# Sallen_key_bandpass.net
KiCad netlist of a schematic drawn in Altium Designer
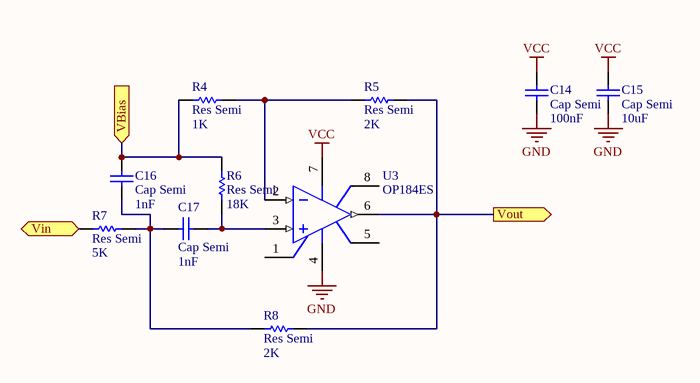
[diagram p0: Sallen_key_bandpass.SchDoc]

(export (version "E")
  (design (tool "Eeschema 10.0.6"))
  (components
    (comp (ref "C14")
      (value "Cap Semi")
      (footprint "C0805")
      (description "Capacitor (Semiconductor SIM Model)")
      (fields (field (name "ALTIUM_VALUE") "100nF") (field (name "PUBLISHER") "Altium Limited"))
      (libsource (lib "Miscellaneous Devices") (part "Cap Semi"))
    )
    (comp (ref "C15")
      (value "Cap Semi")
      (footprint "C1206")
      (description "Capacitor (Semiconductor SIM Model)")
      (fields (field (name "ALTIUM_VALUE") "10uF") (field (name "PUBLISHER") "Altium Limited"))
      (libsource (lib "Miscellaneous Devices") (part "Cap Semi"))
    )
    (comp (ref "C16")
      (value "Cap Semi")
      (footprint "C0805")
      (description "Capacitor (Semiconductor SIM Model)")
      (fields (field (name "ALTIUM_VALUE") "1nF") (field (name "PUBLISHER") "Altium Limited"))
      (libsource (lib "Miscellaneous Devices") (part "Cap Semi"))
    )
    (comp (ref "C17")
      (value "Cap Semi")
      (footprint "C0805")
      (description "Capacitor (Semiconductor SIM Model)")
      (fields (field (name "ALTIUM_VALUE") "1nF") (field (name "PUBLISHER") "Altium Limited"))
      (libsource (lib "Miscellaneous Devices") (part "Cap Semi"))
    )
    (comp (ref "R4")
      (value "Res Semi")
      (footprint "6-0805_M")
      (description "Semiconductor Resistor")
      (fields (field (name "ALTIUM_VALUE") "1K") (field (name "PUBLISHER") "Altium Limited"))
      (libsource (lib "Miscellaneous Devices") (part "Res Semi"))
    )
    (comp (ref "R5")
      (value "Res Semi")
      (footprint "6-0805_M")
      (description "Semiconductor Resistor")
      (fields (field (name "ALTIUM_VALUE") "2K") (field (name "PUBLISHER") "Altium Limited"))
      (libsource (lib "Miscellaneous Devices") (part "Res Semi"))
    )
    (comp (ref "R6")
      (value "Res Semi")
      (footprint "6-0805_M")
      (description "Semiconductor Resistor")
      (fields (field (name "ALTIUM_VALUE") "18K") (field (name "PUBLISHER") "Altium Limited"))
      (libsource (lib "Miscellaneous Devices") (part "Res Semi"))
    )
    (comp (ref "R7")
      (value "Res Semi")
      (footprint "6-0805_M")
      (description "Semiconductor Resistor")
      (fields (field (name "ALTIUM_VALUE") "5K") (field (name "PUBLISHER") "Altium Limited"))
      (libsource (lib "Miscellaneous Devices") (part "Res Semi"))
    )
    (comp (ref "R8")
      (value "Res Semi")
      (footprint "6-0805_M")
      (description "Semiconductor Resistor")
      (fields (field (name "ALTIUM_VALUE") "2K") (field (name "PUBLISHER") "Altium Limited"))
      (libsource (lib "Miscellaneous Devices") (part "Res Semi"))
    )
    (comp (ref "U3")
      (value "OP184ES")
      (footprint "SO-8")
      (description "Precision Rail-to-Rail Input and Ouput Operational Amplifier")
      (fields (field (name "PUBLISHER") "Altium Limited"))
      (libsource (lib "AD Operational Amplifier") (part "OP184ES"))
    )
  )
  (nets
    (net (code "1") (name "/VBias") (class "Default")
      (node (ref "C16") (pin "2") (pinfunction "2_2") (pintype "passive"))
      (node (ref "R4") (pin "1") (pinfunction "1_1") (pintype "passive"))
      (node (ref "R6") (pin "2") (pinfunction "2_2") (pintype "passive"))
    )
    (net (code "2") (name "/Vin") (class "Default")
      (node (ref "R7") (pin "1") (pinfunction "1_1") (pintype "passive"))
    )
    (net (code "3") (name "/Vout") (class "Default")
      (node (ref "R5") (pin "2") (pinfunction "2_2") (pintype "passive"))
      (node (ref "R8") (pin "2") (pinfunction "2_2") (pintype "passive"))
      (node (ref "U3") (pin "6") (pinfunction "OUT_6") (pintype "output"))
    )
    (net (code "4") (name "GND") (class "Default")
      (node (ref "C14") (pin "1") (pinfunction "1_1") (pintype "passive"))
      (node (ref "C15") (pin "1") (pinfunction "1_1") (pintype "passive"))
      (node (ref "U3") (pin "4") (pinfunction "V-_4") (pintype "power_in"))
    )
    (net (code "5") (name "Net-(C16-Pad1)") (class "Default")
      (node (ref "C16") (pin "1") (pinfunction "1_1") (pintype "passive"))
      (node (ref "C17") (pin "2") (pinfunction "2_2") (pintype "passive"))
      (node (ref "R7") (pin "2") (pinfunction "2_2") (pintype "passive"))
      (node (ref "R8") (pin "1") (pinfunction "1_1") (pintype "passive"))
    )
    (net (code "6") (name "Net-(U3-IN+)") (class "Default")
      (node (ref "C17") (pin "1") (pinfunction "1_1") (pintype "passive"))
      (node (ref "R6") (pin "1") (pinfunction "1_1") (pintype "passive"))
      (node (ref "U3") (pin "3") (pinfunction "IN+_3") (pintype "input"))
    )
    (net (code "7") (name "Net-(U3-IN-)") (class "Default")
      (node (ref "R4") (pin "2") (pinfunction "2_2") (pintype "passive"))
      (node (ref "R5") (pin "1") (pinfunction "1_1") (pintype "passive"))
      (node (ref "U3") (pin "2") (pinfunction "IN-_2") (pintype "input"))
    )
    (net (code "8") (name "VCC") (class "Default")
      (node (ref "C14") (pin "2") (pinfunction "2_2") (pintype "passive"))
      (node (ref "C15") (pin "2") (pinfunction "2_2") (pintype "passive"))
      (node (ref "U3") (pin "7") (pinfunction "V+_7") (pintype "power_in"))
    )
    (net (code "9") (name "unconnected-(U3-NC-Pad8)") (class "Default")
      (node (ref "U3") (pin "8") (pinfunction "NC_8") (pintype "passive"))
    )
    (net (code "10") (name "unconnected-(U3-NUL-Pad1)") (class "Default")
      (node (ref "U3") (pin "1") (pinfunction "NUL_1") (pintype "passive"))
    )
    (net (code "11") (name "unconnected-(U3-NUL-Pad5)") (class "Default")
      (node (ref "U3") (pin "5") (pinfunction "NUL_5") (pintype "passive"))
    )
  )
)
